# dongle.net
KiCad netlist of a schematic drawn in Altium Designer
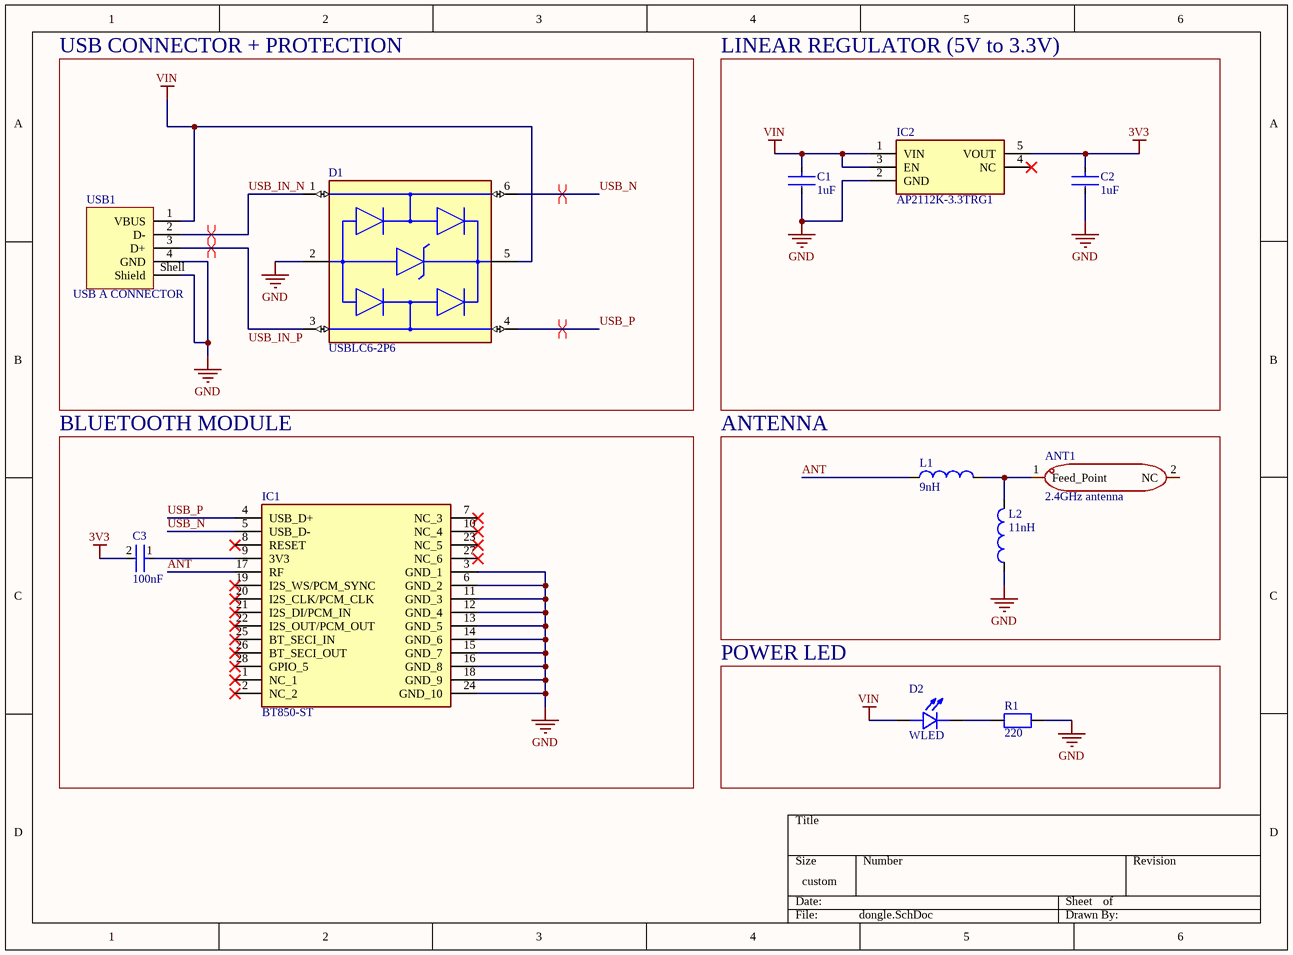
[diagram p0:  dongle.SchDoc]

(export (version "E")
  (design (tool "Eeschema 10.0.6"))
  (components
    (comp (ref "ANT1")
      (value "2.4GHz antenna")
      (footprint "2.4GHz antenna")
      (libsource (lib "schematiclibrary") (part "2.4GHz antenna"))
    )
    (comp (ref "C1")
      (value "1uF")
      (footprint "0402 capacitor")
      (description "0402 smd capacitor")
      (libsource (lib "") (part "0402 capacitor_1"))
    )
    (comp (ref "C2")
      (value "1uF")
      (footprint "0402 capacitor")
      (description "0402 smd capacitor")
      (libsource (lib "") (part "0402 capacitor_1"))
    )
    (comp (ref "C3")
      (value "100nF")
      (footprint "0402 capacitor")
      (description "0402 smd capacitor")
      (libsource (lib "schematiclibrary") (part "0402 capacitor"))
    )
    (comp (ref "D1")
      (value "USBLC6-2P6")
      (footprint "FP-SOT-666-MFG")
      (description "TVS DIODE 5.25V 17V SOT666")
      (libsource (lib "Altium Content Vault") (part "c871e55f7e3243d341edbd671b98d92"))
    )
    (comp (ref "D2")
      (value "WLED")
      (footprint "LED_KT-0603R")
      (description "Red 0603 Light Emitting Diodes")
      (fields (field (name "MF") "Hubei KENTO Elec") (field (name "MP") "KT-0603R"))
      (libsource (lib "KT-0603R") (part "KT-0603R"))
    )
    (comp (ref "IC1")
      (value "BT850-ST")
      (footprint "BT850-ST")
      (libsource (lib "schematiclibrary") (part "BT850-ST"))
    )
    (comp (ref "IC2")
      (value "AP2112K-3.3TRG1")
      (footprint "SamacSys:SOT95P285X140-5N")
      (description "Integrated Circuit")
      (fields (field (name "MOUSER PART NUMBER") "621-AP2112K-3.3TRG1"))
      (libsource (lib "SamacSys") (part "AP2112K-3.3TRG1"))
    )
    (comp (ref "L1")
      (value "9nH")
      (footprint "0402INDUCTOR")
      (libsource (lib "schematiclibrary") (part "0402 inductor"))
    )
    (comp (ref "L2")
      (value "11nH")
      (footprint "0402INDUCTOR")
      (libsource (lib "schematiclibrary") (part "0402 inductor"))
    )
    (comp (ref "R1")
      (value "220")
      (footprint "0402 resistor")
      (libsource (lib "schematiclibrary") (part "0402 resistor"))
    )
    (comp (ref "USB1")
      (value "USB A CONNECTOR")
      (footprint "USB A CONNECTOR RECESSED")
      (libsource (lib "schematiclibrary") (part "USB A CONNECTOR RECESSED"))
    )
  )
  (nets
    (net (code "1") (name "/ANT") (class "Default")
      (node (ref "IC1") (pin "17") (pinfunction "RF_17") (pintype "passive"))
      (node (ref "L1") (pin "1") (pinfunction "1_1") (pintype "passive"))
    )
    (net (code "2") (name "/USB_IN_N") (class "Default")
      (node (ref "D1") (pin "1") (pinfunction "I/O1_1") (pintype "bidirectional"))
      (node (ref "USB1") (pin "2") (pinfunction "D-_2") (pintype "passive"))
    )
    (net (code "3") (name "/USB_IN_P") (class "Default")
      (node (ref "D1") (pin "3") (pinfunction "I/O2_3") (pintype "bidirectional"))
      (node (ref "USB1") (pin "3") (pinfunction "D+_3") (pintype "passive"))
    )
    (net (code "4") (name "/USB_N") (class "Default")
      (node (ref "D1") (pin "6") (pinfunction "I/O1_6") (pintype "bidirectional"))
      (node (ref "IC1") (pin "5") (pinfunction "USB_D-_5") (pintype "passive"))
    )
    (net (code "5") (name "/USB_P") (class "Default")
      (node (ref "D1") (pin "4") (pinfunction "I/O2_4") (pintype "bidirectional"))
      (node (ref "IC1") (pin "4") (pinfunction "USB_D+_4") (pintype "passive"))
    )
    (net (code "6") (name "3V3") (class "Default")
      (node (ref "C2") (pin "1") (pinfunction "1_1") (pintype "passive"))
      (node (ref "C3") (pin "2") (pinfunction "2_2") (pintype "passive"))
      (node (ref "IC2") (pin "5") (pinfunction "VOUT_5") (pintype "passive"))
    )
    (net (code "7") (name "GND") (class "Default")
      (node (ref "C1") (pin "2") (pinfunction "2_2") (pintype "passive"))
      (node (ref "C2") (pin "2") (pinfunction "2_2") (pintype "passive"))
      (node (ref "D1") (pin "2") (pinfunction "GND_2") (pintype "power_in"))
      (node (ref "IC1") (pin "11") (pinfunction "GND_3_11") (pintype "passive"))
      (node (ref "IC1") (pin "12") (pinfunction "GND_4_12") (pintype "passive"))
      (node (ref "IC1") (pin "13") (pinfunction "GND_5_13") (pintype "passive"))
      (node (ref "IC1") (pin "14") (pinfunction "GND_6_14") (pintype "passive"))
      (node (ref "IC1") (pin "15") (pinfunction "GND_7_15") (pintype "passive"))
      (node (ref "IC1") (pin "16") (pinfunction "GND_8_16") (pintype "passive"))
      (node (ref "IC1") (pin "18") (pinfunction "GND_9_18") (pintype "passive"))
      (node (ref "IC1") (pin "24") (pinfunction "GND_10_24") (pintype "passive"))
      (node (ref "IC1") (pin "3") (pinfunction "GND_1_3") (pintype "passive"))
      (node (ref "IC1") (pin "6") (pinfunction "GND_2_6") (pintype "passive"))
      (node (ref "IC2") (pin "2") (pinfunction "GND_2") (pintype "passive"))
      (node (ref "L2") (pin "1") (pinfunction "1_1") (pintype "passive"))
      (node (ref "R1") (pin "2") (pinfunction "12_2") (pintype "passive"))
      (node (ref "USB1") (pin "4") (pinfunction "GND_4") (pintype "passive"))
      (node (ref "USB1") (pin "Shell") (pinfunction "Shield_Shell") (pintype "passive"))
    )
    (net (code "8") (name "Net-(ANT1-Feed_Point)") (class "Default")
      (node (ref "ANT1") (pin "1") (pinfunction "Feed_Point_1") (pintype "passive"))
      (node (ref "L1") (pin "2") (pinfunction "2_2") (pintype "passive"))
      (node (ref "L2") (pin "2") (pinfunction "2_2") (pintype "passive"))
    )
    (net (code "9") (name "Net-(IC1-3V3)") (class "Default")
      (node (ref "C3") (pin "1") (pinfunction "1_1") (pintype "passive"))
      (node (ref "IC1") (pin "9") (pinfunction "3V3_9") (pintype "passive"))
    )
    (net (code "10") (name "Net-(R1-11)") (class "Default")
      (node (ref "D2") (pin "C") (pinfunction "C_C") (pintype "passive"))
      (node (ref "R1") (pin "1") (pinfunction "11_1") (pintype "passive"))
    )
    (net (code "11") (name "VIN") (class "Default")
      (node (ref "C1") (pin "1") (pinfunction "1_1") (pintype "passive"))
      (node (ref "D1") (pin "5") (pinfunction "VBUS_5") (pintype "power_in"))
      (node (ref "D2") (pin "A") (pinfunction "A_A") (pintype "passive"))
      (node (ref "IC2") (pin "1") (pinfunction "VIN_1") (pintype "passive"))
      (node (ref "IC2") (pin "3") (pinfunction "EN_3") (pintype "passive"))
      (node (ref "USB1") (pin "1") (pinfunction "VBUS_1") (pintype "passive"))
    )
    (net (code "12") (name "unconnected-(ANT1-NC-Pad2)") (class "Default")
      (node (ref "ANT1") (pin "2") (pinfunction "NC_2") (pintype "passive"))
    )
    (net (code "13") (name "unconnected-(IC1-BT_SECI_IN-Pad25)") (class "Default")
      (node (ref "IC1") (pin "25") (pinfunction "BT_SECI_IN_25") (pintype "passive+no_connect"))
    )
    (net (code "14") (name "unconnected-(IC1-BT_SECI_OUT-Pad26)") (class "Default")
      (node (ref "IC1") (pin "26") (pinfunction "BT_SECI_OUT_26") (pintype "passive+no_connect"))
    )
    (net (code "15") (name "unconnected-(IC1-GPIO_5-Pad28)") (class "Default")
      (node (ref "IC1") (pin "28") (pinfunction "GPIO_5_28") (pintype "passive+no_connect"))
    )
    (net (code "16") (name "unconnected-(IC1-I2S_CLK{slash}PCM_CLK-Pad20)") (class "Default")
      (node (ref "IC1") (pin "20") (pinfunction "I2S_CLK/PCM_CLK_20") (pintype "passive+no_connect"))
    )
    (net (code "17") (name "unconnected-(IC1-I2S_DI{slash}PCM_IN-Pad21)") (class "Default")
      (node (ref "IC1") (pin "21") (pinfunction "I2S_DI/PCM_IN_21") (pintype "passive+no_connect"))
    )
    (net (code "18") (name "unconnected-(IC1-I2S_OUT{slash}PCM_OUT-Pad22)") (class "Default")
      (node (ref "IC1") (pin "22") (pinfunction "I2S_OUT/PCM_OUT_22") (pintype "passive+no_connect"))
    )
    (net (code "19") (name "unconnected-(IC1-I2S_WS{slash}PCM_SYNC-Pad19)") (class "Default")
      (node (ref "IC1") (pin "19") (pinfunction "I2S_WS/PCM_SYNC_19") (pintype "passive+no_connect"))
    )
    (net (code "20") (name "unconnected-(IC1-NC_1-Pad1)") (class "Default")
      (node (ref "IC1") (pin "1") (pinfunction "NC_1_1") (pintype "passive+no_connect"))
    )
    (net (code "21") (name "unconnected-(IC1-NC_2-Pad2)") (class "Default")
      (node (ref "IC1") (pin "2") (pinfunction "NC_2_2") (pintype "passive+no_connect"))
    )
    (net (code "22") (name "unconnected-(IC1-NC_3-Pad7)") (class "Default")
      (node (ref "IC1") (pin "7") (pinfunction "NC_3_7") (pintype "passive+no_connect"))
    )
    (net (code "23") (name "unconnected-(IC1-NC_4-Pad10)") (class "Default")
      (node (ref "IC1") (pin "10") (pinfunction "NC_4_10") (pintype "passive+no_connect"))
    )
    (net (code "24") (name "unconnected-(IC1-NC_5-Pad23)") (class "Default")
      (node (ref "IC1") (pin "23") (pinfunction "NC_5_23") (pintype "passive+no_connect"))
    )
    (net (code "25") (name "unconnected-(IC1-NC_6-Pad27)") (class "Default")
      (node (ref "IC1") (pin "27") (pinfunction "NC_6_27") (pintype "passive+no_connect"))
    )
    (net (code "26") (name "unconnected-(IC1-RESET-Pad8)") (class "Default")
      (node (ref "IC1") (pin "8") (pinfunction "RESET_8") (pintype "passive+no_connect"))
    )
    (net (code "27") (name "unconnected-(IC2-NC-Pad4)") (class "Default")
      (node (ref "IC2") (pin "4") (pinfunction "NC_4") (pintype "passive+no_connect"))
    )
  )
)
